# SCH_step-count_2025-07-05.net
KiCad netlist of a schematic drawn in EasyEDA
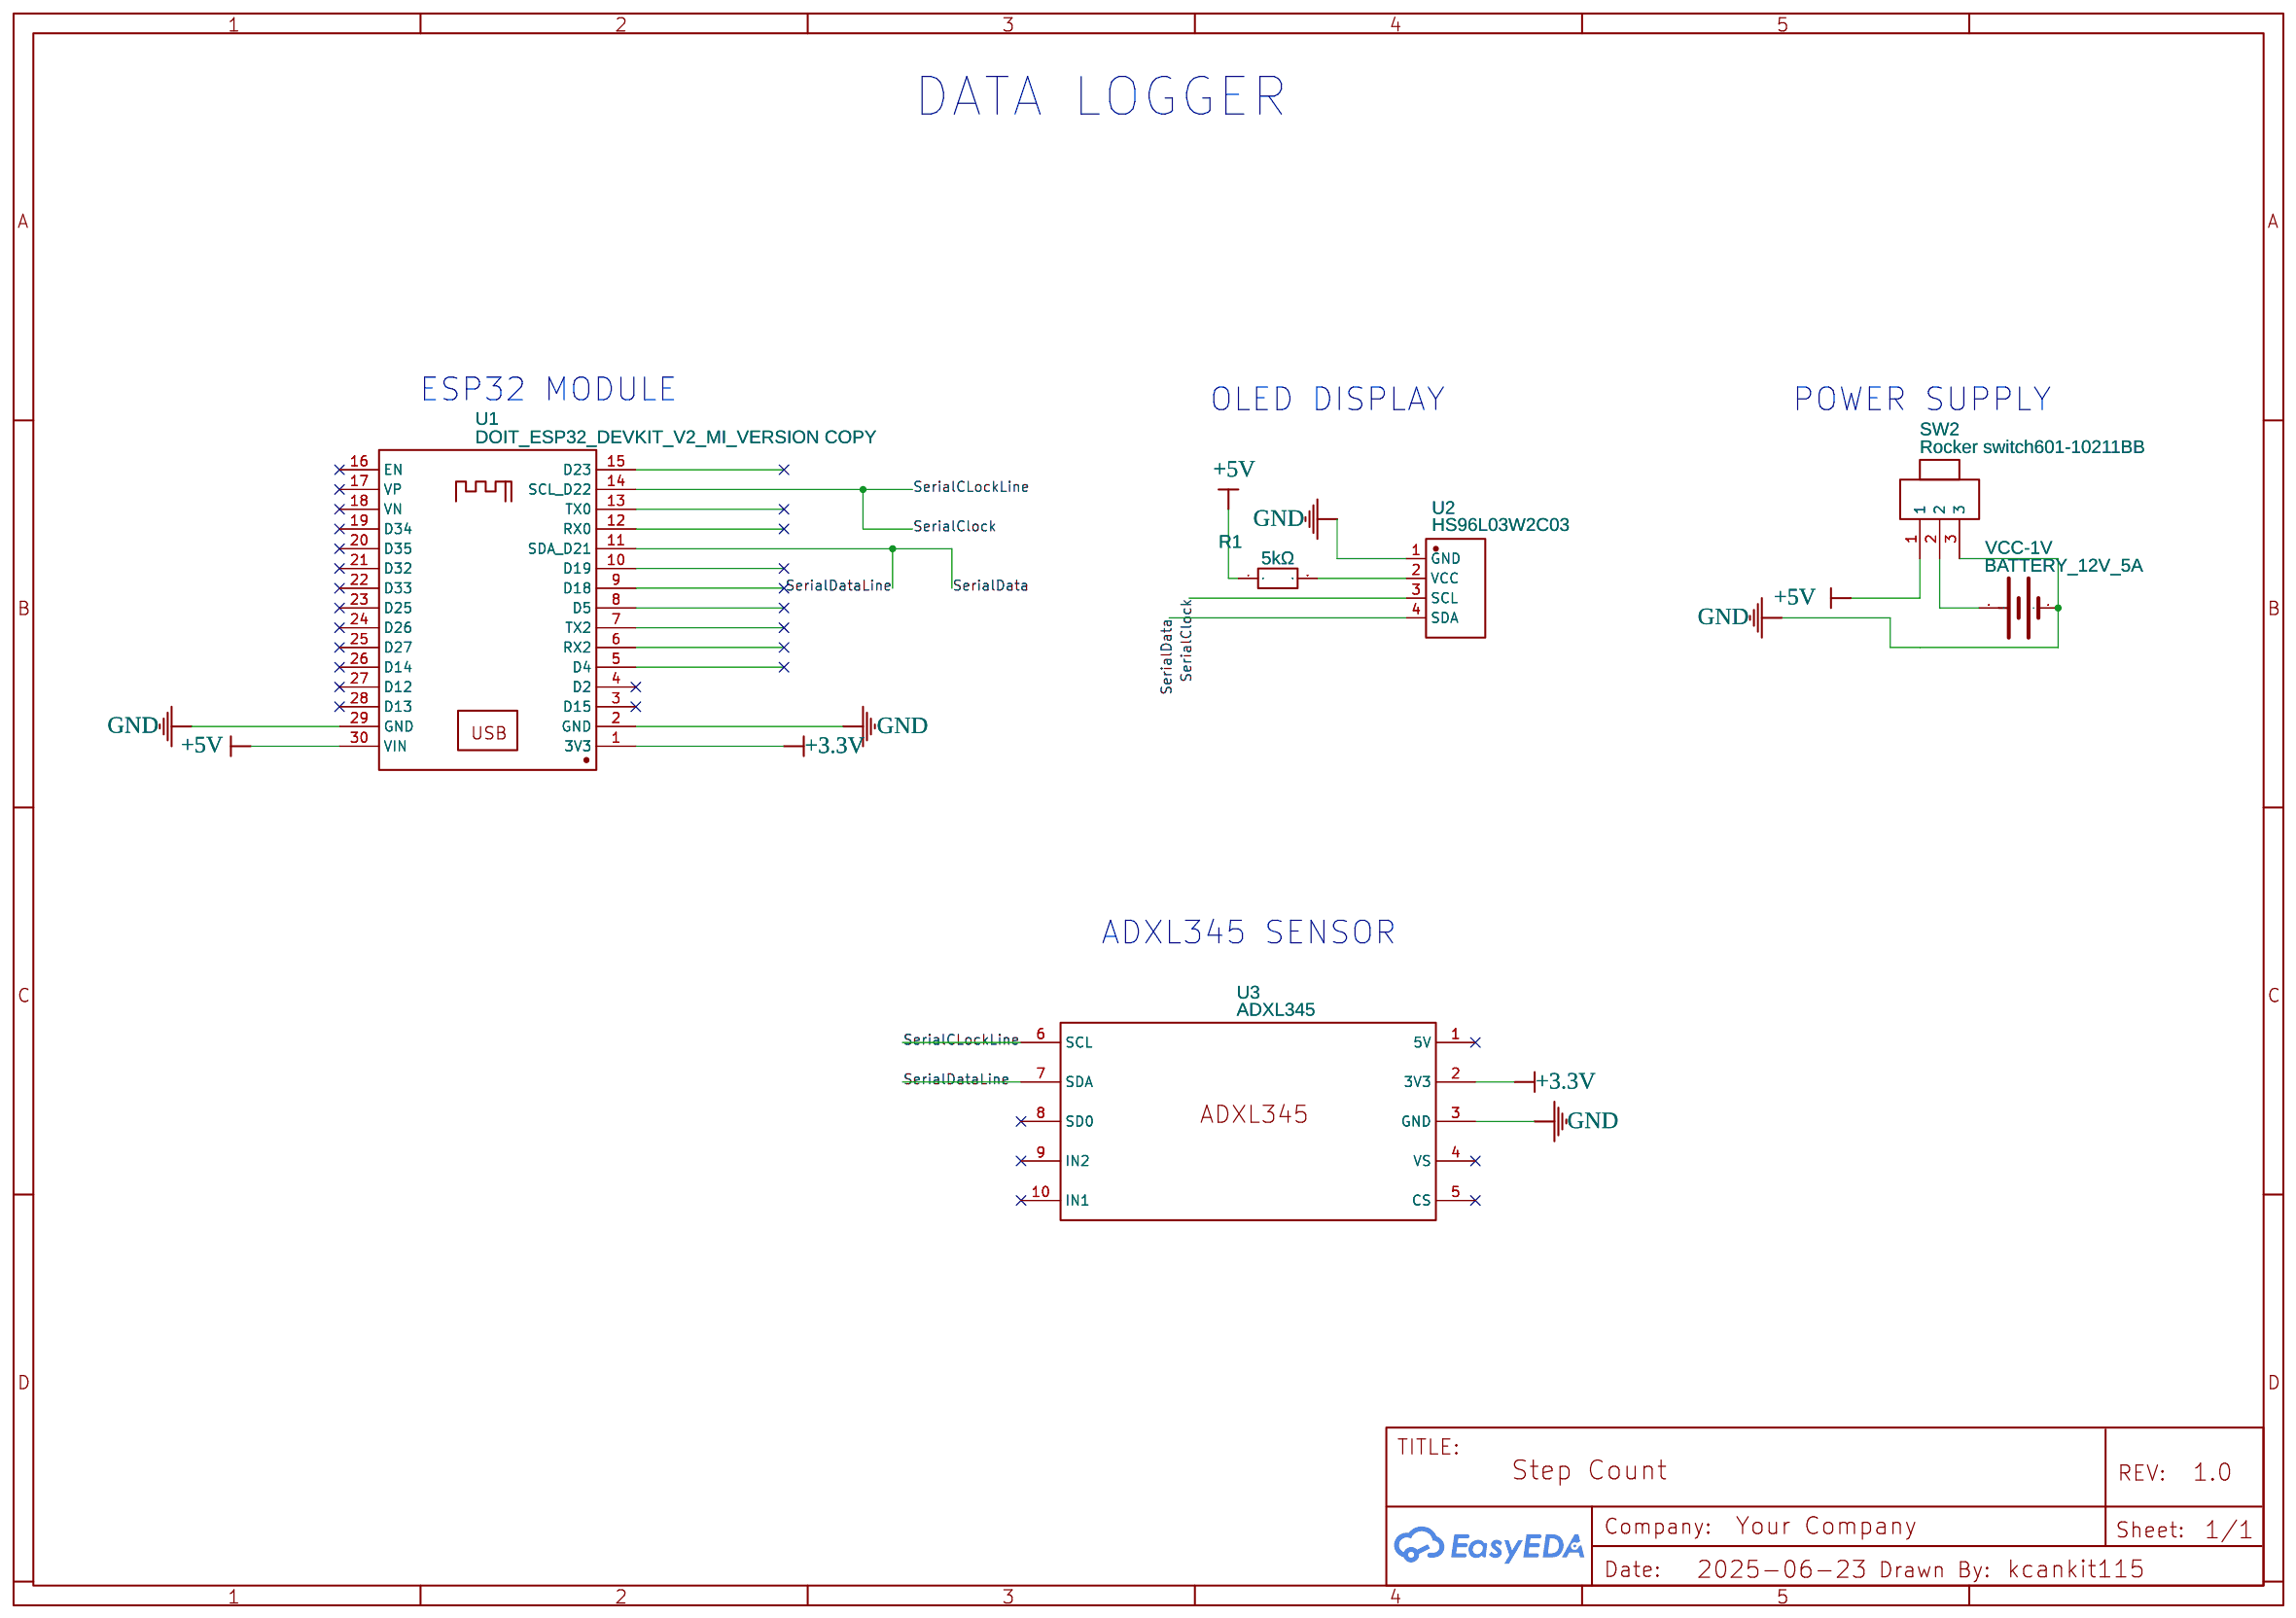
[diagram p0: schematic sheet]

(export (version "E")
  (design (tool "Eeschema 10.0.6"))
  (components
    (comp (ref "R1")
      (value "5kΩ")
      (fields (field (name "Manufacturer Part") "MF1/4W-1KΩ±1%T52") (field (name "Manufacturer") "华星机电"))
      (libsource (lib "") (part "MF1/4W-1KΩ±1%T52 COPY"))
    )
    (comp (ref "SW2")
      (value "Rocker switch601-10211BB")
      (fields (field (name "Manufacturer") "BBJ"))
      (libsource (lib "") (part "Rocker switch601-10211BB"))
    )
    (comp (ref "U1")
      (value "DOIT_ESP32_DEVKIT_V2_MI_VERSION COPY")
      (libsource (lib "") (part "DOIT_ESP32_DEVKIT_V2_MI_VERSION COPY"))
    )
    (comp (ref "U2")
      (value "HS96L03W2C03")
      (fields (field (name "Manufacturer") "HS(汉昇)"))
      (libsource (lib "") (part "HS96L03W2C03"))
    )
    (comp (ref "U3") (value "ADXL345") (libsource (lib "") (part "ADXL345")))
    (comp (ref "VCC-1V")
      (value "BATTERY_12V_5A")
      (fields (field (name "Manufacturer Part") "BATTERY_12A_27A"))
      (libsource (lib "") (part "BATTERY_12A_27A"))
    )
  )
  (nets
    (net (code "1") (name "+3.3V") (class "Default")
      (node (ref "U1") (pin "1") (pinfunction "3V3_1") (pintype "unspecified"))
      (node (ref "U3") (pin "2") (pinfunction "3V3_2") (pintype "unspecified"))
    )
    (net (code "2") (name "+5V") (class "Default")
      (node (ref "R1") (pin "1") (pinfunction "1_1") (pintype "unspecified"))
      (node (ref "SW2") (pin "1") (pinfunction "1_1") (pintype "unspecified"))
      (node (ref "U1") (pin "30") (pinfunction "VIN_30") (pintype "unspecified"))
    )
    (net (code "3") (name "/SerialCLockLine") (class "Default")
      (node (ref "U1") (pin "14") (pinfunction "SCL_D22_14") (pintype "unspecified"))
      (node (ref "U2") (pin "3") (pinfunction "SCL_3") (pintype "unspecified"))
      (node (ref "U3") (pin "6") (pinfunction "SCL_6") (pintype "unspecified"))
    )
    (net (code "4") (name "/SerialData") (class "Default")
      (node (ref "U1") (pin "11") (pinfunction "SDA_D21_11") (pintype "unspecified"))
      (node (ref "U2") (pin "4") (pinfunction "SDA_4") (pintype "unspecified"))
      (node (ref "U3") (pin "7") (pinfunction "SDA_7") (pintype "unspecified"))
    )
    (net (code "5") (name "GND") (class "Default")
      (node (ref "SW2") (pin "3") (pinfunction "3_3") (pintype "unspecified"))
      (node (ref "U1") (pin "2") (pinfunction "GND_2") (pintype "unspecified"))
      (node (ref "U1") (pin "29") (pinfunction "GND_29") (pintype "unspecified"))
      (node (ref "U2") (pin "1") (pinfunction "GND_1") (pintype "unspecified"))
      (node (ref "U3") (pin "3") (pinfunction "GND_3") (pintype "unspecified"))
      (node (ref "VCC-1V") (pin "1") (pinfunction "-_1") (pintype "unspecified"))
    )
    (net (code "6") (name "Net-(U2-VCC)") (class "Default")
      (node (ref "R1") (pin "2") (pinfunction "2_2") (pintype "unspecified"))
      (node (ref "U2") (pin "2") (pinfunction "VCC_2") (pintype "unspecified"))
    )
    (net (code "7") (name "Net-(VCC-1V-+)") (class "Default")
      (node (ref "SW2") (pin "2") (pinfunction "2_2") (pintype "unspecified"))
      (node (ref "VCC-1V") (pin "2") (pinfunction "+_2") (pintype "unspecified"))
    )
    (net (code "8") (name "unconnected-(U1-D2-Pad4)") (class "Default")
      (node (ref "U1") (pin "4") (pinfunction "D2_4") (pintype "unspecified+no_connect"))
    )
    (net (code "9") (name "unconnected-(U1-D4-Pad5)") (class "Default")
      (node (ref "U1") (pin "5") (pinfunction "D4_5") (pintype "unspecified+no_connect"))
    )
    (net (code "10") (name "unconnected-(U1-D5-Pad8)") (class "Default")
      (node (ref "U1") (pin "8") (pinfunction "D5_8") (pintype "unspecified+no_connect"))
    )
    (net (code "11") (name "unconnected-(U1-D12-Pad27)") (class "Default")
      (node (ref "U1") (pin "27") (pinfunction "D12_27") (pintype "unspecified+no_connect"))
    )
    (net (code "12") (name "unconnected-(U1-D13-Pad28)") (class "Default")
      (node (ref "U1") (pin "28") (pinfunction "D13_28") (pintype "unspecified+no_connect"))
    )
    (net (code "13") (name "unconnected-(U1-D14-Pad26)") (class "Default")
      (node (ref "U1") (pin "26") (pinfunction "D14_26") (pintype "unspecified+no_connect"))
    )
    (net (code "14") (name "unconnected-(U1-D15-Pad3)") (class "Default")
      (node (ref "U1") (pin "3") (pinfunction "D15_3") (pintype "unspecified+no_connect"))
    )
    (net (code "15") (name "unconnected-(U1-D18-Pad9)") (class "Default")
      (node (ref "U1") (pin "9") (pinfunction "D18_9") (pintype "unspecified+no_connect"))
    )
    (net (code "16") (name "unconnected-(U1-D19-Pad10)") (class "Default")
      (node (ref "U1") (pin "10") (pinfunction "D19_10") (pintype "unspecified+no_connect"))
    )
    (net (code "17") (name "unconnected-(U1-D23-Pad15)") (class "Default")
      (node (ref "U1") (pin "15") (pinfunction "D23_15") (pintype "unspecified+no_connect"))
    )
    (net (code "18") (name "unconnected-(U1-D25-Pad23)") (class "Default")
      (node (ref "U1") (pin "23") (pinfunction "D25_23") (pintype "unspecified+no_connect"))
    )
    (net (code "19") (name "unconnected-(U1-D26-Pad24)") (class "Default")
      (node (ref "U1") (pin "24") (pinfunction "D26_24") (pintype "unspecified+no_connect"))
    )
    (net (code "20") (name "unconnected-(U1-D27-Pad25)") (class "Default")
      (node (ref "U1") (pin "25") (pinfunction "D27_25") (pintype "unspecified+no_connect"))
    )
    (net (code "21") (name "unconnected-(U1-D32-Pad21)") (class "Default")
      (node (ref "U1") (pin "21") (pinfunction "D32_21") (pintype "unspecified+no_connect"))
    )
    (net (code "22") (name "unconnected-(U1-D33-Pad22)") (class "Default")
      (node (ref "U1") (pin "22") (pinfunction "D33_22") (pintype "unspecified+no_connect"))
    )
    (net (code "23") (name "unconnected-(U1-D34-Pad19)") (class "Default")
      (node (ref "U1") (pin "19") (pinfunction "D34_19") (pintype "unspecified+no_connect"))
    )
    (net (code "24") (name "unconnected-(U1-D35-Pad20)") (class "Default")
      (node (ref "U1") (pin "20") (pinfunction "D35_20") (pintype "unspecified+no_connect"))
    )
    (net (code "25") (name "unconnected-(U1-EN-Pad16)") (class "Default")
      (node (ref "U1") (pin "16") (pinfunction "EN_16") (pintype "unspecified+no_connect"))
    )
    (net (code "26") (name "unconnected-(U1-RX0-Pad12)") (class "Default")
      (node (ref "U1") (pin "12") (pinfunction "RX0_12") (pintype "unspecified+no_connect"))
    )
    (net (code "27") (name "unconnected-(U1-RX2-Pad6)") (class "Default")
      (node (ref "U1") (pin "6") (pinfunction "RX2_6") (pintype "unspecified+no_connect"))
    )
    (net (code "28") (name "unconnected-(U1-TX0-Pad13)") (class "Default")
      (node (ref "U1") (pin "13") (pinfunction "TX0_13") (pintype "unspecified+no_connect"))
    )
    (net (code "29") (name "unconnected-(U1-TX2-Pad7)") (class "Default")
      (node (ref "U1") (pin "7") (pinfunction "TX2_7") (pintype "unspecified+no_connect"))
    )
    (net (code "30") (name "unconnected-(U1-VN-Pad18)") (class "Default")
      (node (ref "U1") (pin "18") (pinfunction "VN_18") (pintype "unspecified+no_connect"))
    )
    (net (code "31") (name "unconnected-(U1-VP-Pad17)") (class "Default")
      (node (ref "U1") (pin "17") (pinfunction "VP_17") (pintype "unspecified+no_connect"))
    )
    (net (code "32") (name "unconnected-(U3-5V-Pad1)") (class "Default")
      (node (ref "U3") (pin "1") (pinfunction "5V_1") (pintype "unspecified+no_connect"))
    )
    (net (code "33") (name "unconnected-(U3-CS-Pad5)") (class "Default")
      (node (ref "U3") (pin "5") (pinfunction "CS_5") (pintype "unspecified+no_connect"))
    )
    (net (code "34") (name "unconnected-(U3-IN1-Pad10)") (class "Default")
      (node (ref "U3") (pin "10") (pinfunction "IN1_10") (pintype "unspecified+no_connect"))
    )
    (net (code "35") (name "unconnected-(U3-IN2-Pad9)") (class "Default")
      (node (ref "U3") (pin "9") (pinfunction "IN2_9") (pintype "unspecified+no_connect"))
    )
    (net (code "36") (name "unconnected-(U3-SD0-Pad8)") (class "Default")
      (node (ref "U3") (pin "8") (pinfunction "SD0_8") (pintype "unspecified+no_connect"))
    )
    (net (code "37") (name "unconnected-(U3-VS-Pad4)") (class "Default")
      (node (ref "U3") (pin "4") (pinfunction "VS_4") (pintype "unspecified+no_connect"))
    )
  )
)
